# VIVA_PIC16_V5.net
KiCad netlist of a schematic drawn in EAGLE
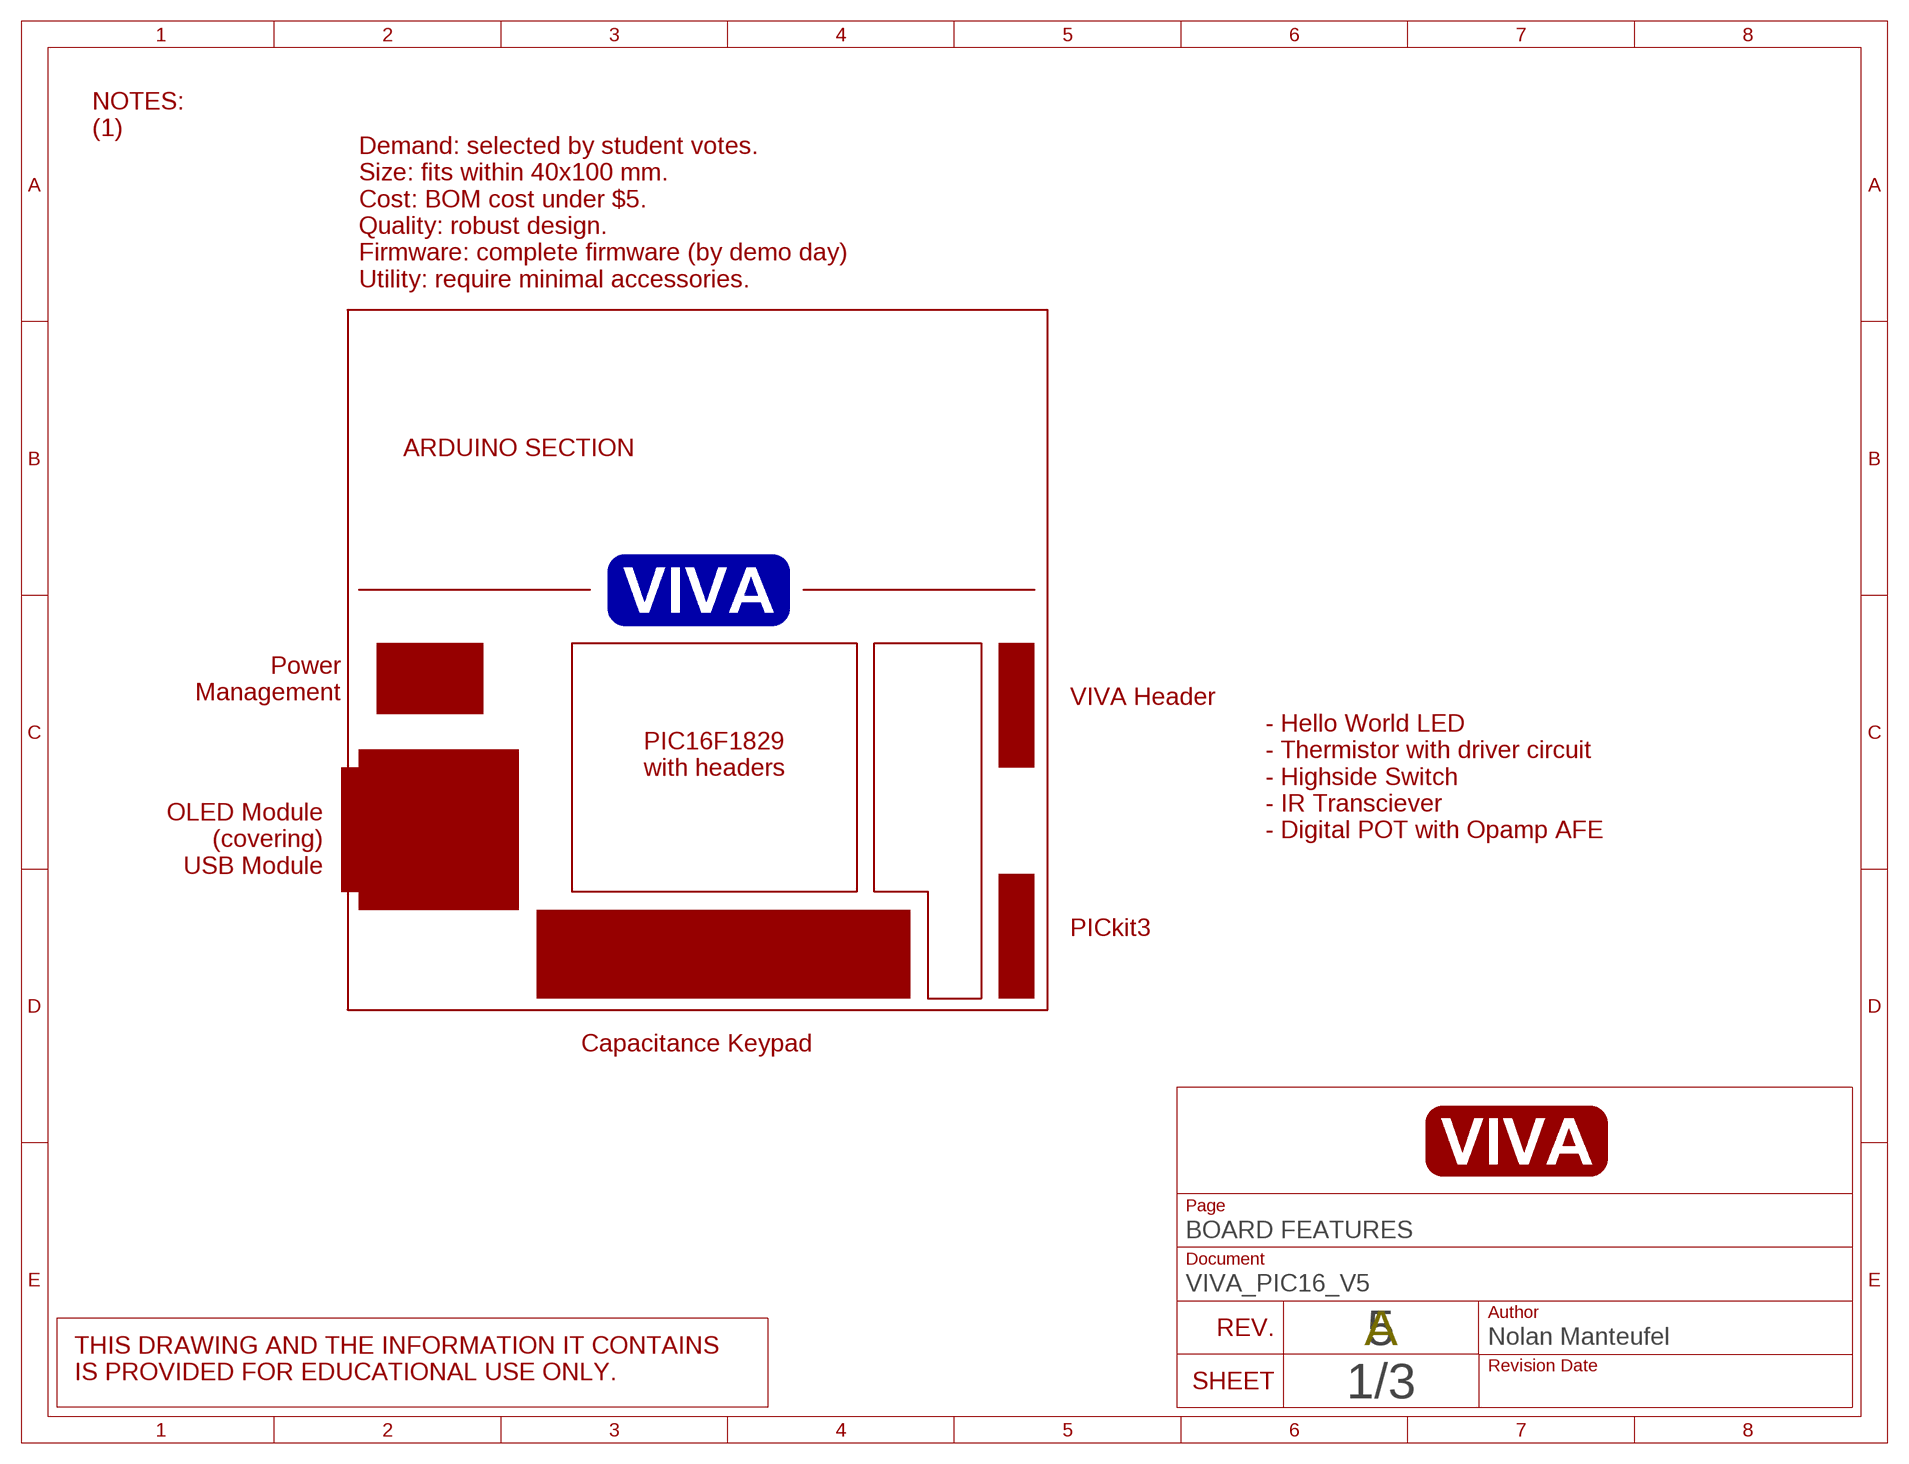
[diagram p0: schematic, sheet 1]
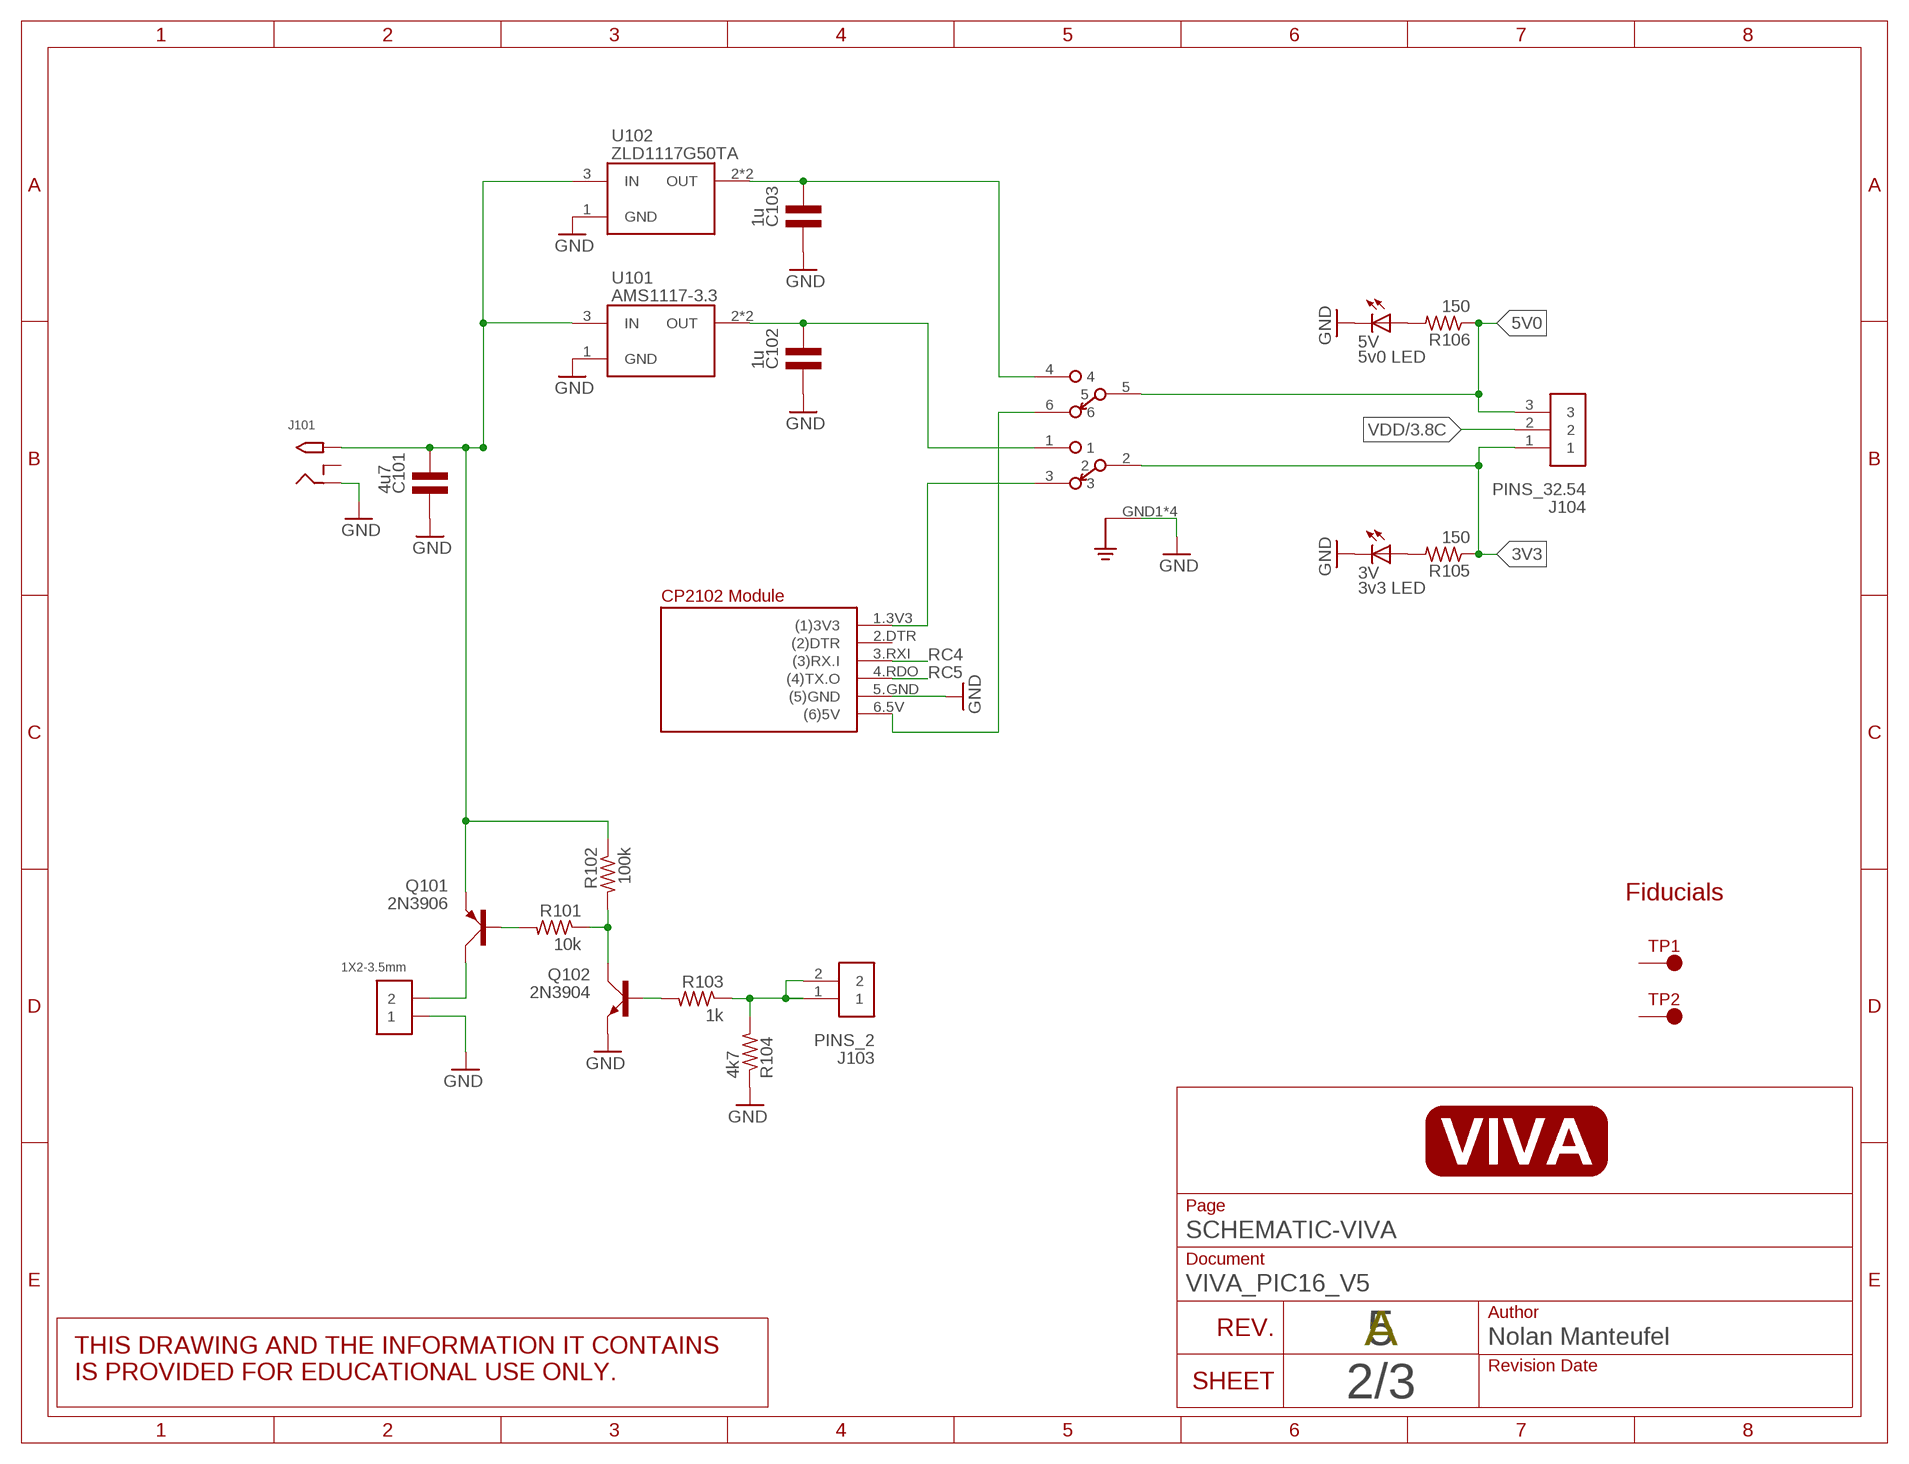
[diagram p1: schematic, sheet 2]
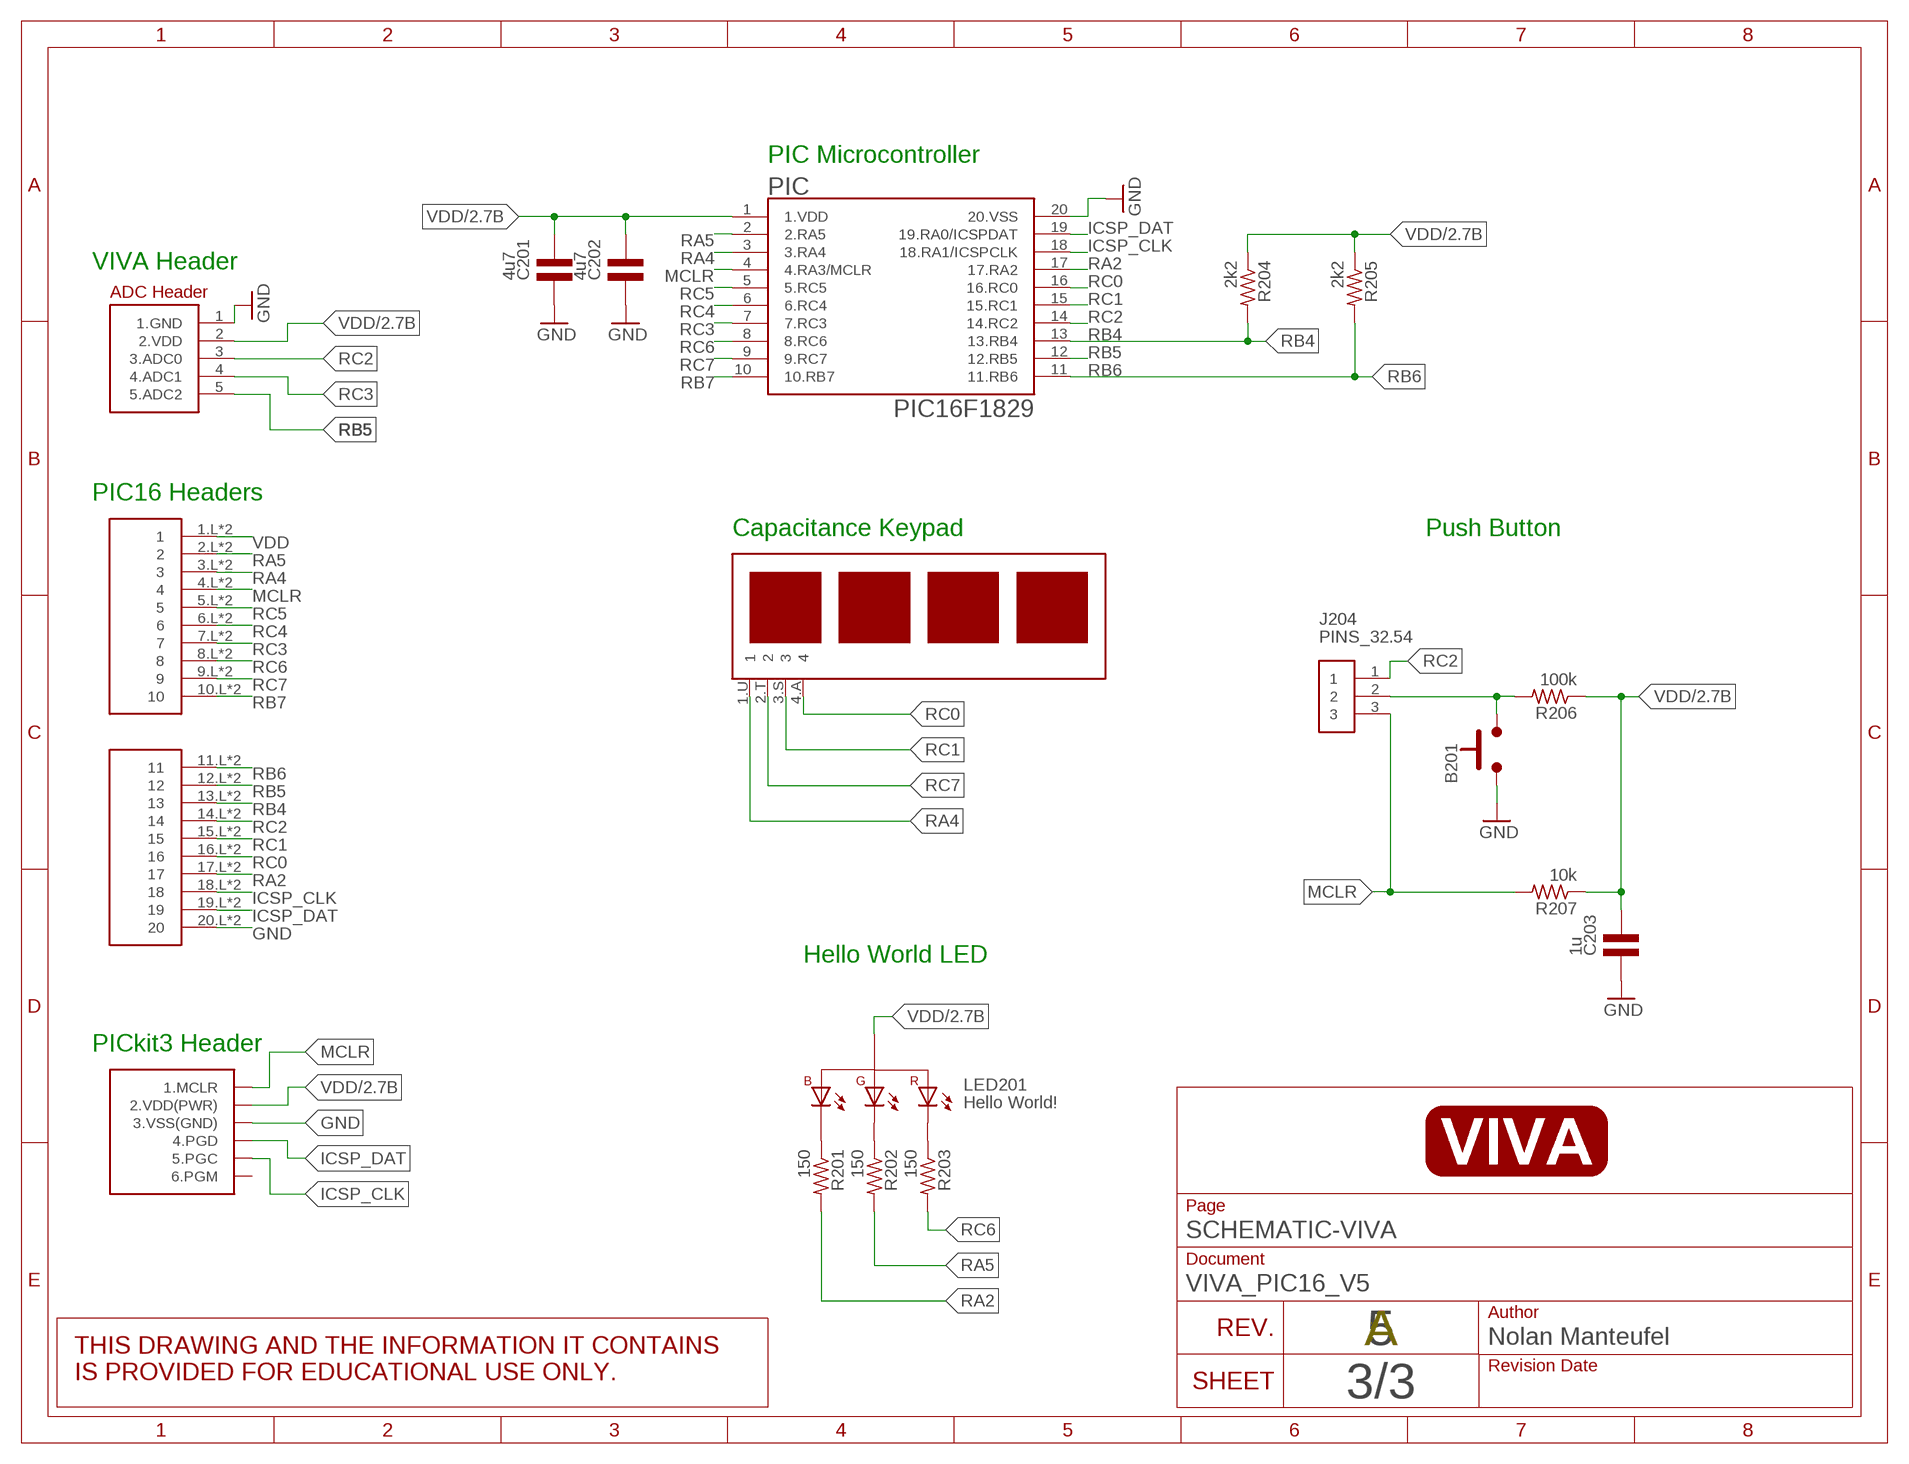
[diagram p2: schematic, sheet 3]

(export (version "E")
  (design (tool "Eeschema 10.0.6"))
  (components
    (comp (ref "U$1")
      (value "VIVA_LOGO")
      (footprint "eagle-import:VIVA_LOGO")
      (libsource (lib "eagle-import") (part "VIVA_LOGO"))
    )
    (comp (ref "B201")
      (value "PUSHBUTTON6X6MM")
      (footprint "eagle-import:6X6MM")
      (libsource (lib "eagle-import") (part "PUSHBUTTON6X6MM"))
    )
    (comp (ref "C201")
      (value "4u7")
      (footprint "eagle-import:C0805")
      (libsource (lib "eagle-import") (part "C0805"))
    )
    (comp (ref "C202")
      (value "4u7")
      (footprint "eagle-import:C0805")
      (libsource (lib "eagle-import") (part "C0805"))
    )
    (comp (ref "C203")
      (value "1u")
      (footprint "eagle-import:C0805")
      (libsource (lib "eagle-import") (part "C0805"))
    )
    (comp (ref "J201")
      (value "VIVA_PIC16")
      (footprint "eagle-import:VIVA_PIC16")
      (libsource (lib "eagle-import") (part "VIVA_PIC16"))
    )
    (comp (ref "J202")
      (value "VIVA-HEADER-ADCNONAME")
      (footprint "eagle-import:VIVA-HEADER-ADC-NONAME")
      (libsource (lib "eagle-import") (part "VIVA-HEADER-ADCNONAME"))
    )
    (comp (ref "J203")
      (value "PICKIT3")
      (footprint "eagle-import:PICKIT3")
      (libsource (lib "eagle-import") (part "PICKIT3"))
    )
    (comp (ref "J204")
      (value "PINS_32.54")
      (footprint "eagle-import:PINS_3")
      (libsource (lib "eagle-import") (part "PINS_32.54"))
    )
    (comp (ref "LED201")
      (value "Hello World!")
      (footprint "eagle-import:LED_RGB-5050")
      (libsource (lib "eagle-import") (part "RGB_LED"))
    )
    (comp (ref "PIC")
      (value "PIC16F1829")
      (footprint "eagle-import:SOP20-NEW")
      (libsource (lib "eagle-import") (part "PIC16F1829"))
    )
    (comp (ref "R201")
      (value "150")
      (footprint "eagle-import:R0805")
      (libsource (lib "eagle-import") (part "R-US_R0805"))
    )
    (comp (ref "R202")
      (value "150")
      (footprint "eagle-import:R0805")
      (libsource (lib "eagle-import") (part "R-US_R0805"))
    )
    (comp (ref "R203")
      (value "150")
      (footprint "eagle-import:R0805")
      (libsource (lib "eagle-import") (part "R-US_R0805"))
    )
    (comp (ref "R204")
      (value "2k2")
      (footprint "eagle-import:R0805")
      (libsource (lib "eagle-import") (part "R-US_R0805"))
    )
    (comp (ref "R205")
      (value "2k2")
      (footprint "eagle-import:R0805")
      (libsource (lib "eagle-import") (part "R-US_R0805"))
    )
    (comp (ref "R206")
      (value "100k")
      (footprint "eagle-import:R0805")
      (libsource (lib "eagle-import") (part "R-US_R0805"))
    )
    (comp (ref "R207")
      (value "10k")
      (footprint "eagle-import:R0805")
      (libsource (lib "eagle-import") (part "R-US_R0805"))
    )
    (comp (ref "U$201")
      (value "VIVA_UTSA-KEYPAD")
      (footprint "eagle-import:VIVA_UTSA-KEYPAD")
      (libsource (lib "eagle-import") (part "VIVA_UTSA-KEYPAD"))
    )
    (comp (ref "3V")
      (value "3v3 LED")
      (footprint "eagle-import:CHIPLED_0805")
      (libsource (lib "eagle-import") (part "LEDCHIPLED_0805"))
    )
    (comp (ref "5V")
      (value "5v0 LED")
      (footprint "eagle-import:CHIPLED_0805")
      (libsource (lib "eagle-import") (part "LEDCHIPLED_0805"))
    )
    (comp (ref "C101")
      (value "4u7")
      (footprint "eagle-import:C0805")
      (libsource (lib "eagle-import") (part "C0805"))
    )
    (comp (ref "C102")
      (value "1u")
      (footprint "eagle-import:C0805")
      (libsource (lib "eagle-import") (part "C0805"))
    )
    (comp (ref "C103")
      (value "1u")
      (footprint "eagle-import:C0805")
      (libsource (lib "eagle-import") (part "C0805"))
    )
    (comp (ref "J101")
      (value "2.1MMJACKTHM")
      (footprint "eagle-import:PJ-102A")
      (libsource (lib "eagle-import") (part "2.1MMJACKTHM"))
    )
    (comp (ref "J102")
      (value "1X2-3.5MM-3.5MM")
      (footprint "eagle-import:1X2-3.5MM")
      (libsource (lib "eagle-import") (part "1X2-3.5MM-3.5MM"))
    )
    (comp (ref "J103")
      (value "PINS_2")
      (footprint "eagle-import:PINS_2")
      (libsource (lib "eagle-import") (part "PINS_2"))
    )
    (comp (ref "J104")
      (value "PINS_32.54")
      (footprint "eagle-import:PINS_3")
      (libsource (lib "eagle-import") (part "PINS_32.54"))
    )
    (comp (ref "M101")
      (value "VIVA_USB-TTL")
      (footprint "eagle-import:VIVA_USB_TTL_SUBTEXT")
      (libsource (lib "eagle-import") (part "VIVA_USB-TTL"))
    )
    (comp (ref "Q101")
      (value "2N3906")
      (footprint "eagle-import:SOT23")
      (libsource (lib "eagle-import") (part "2N3906SOT23"))
    )
    (comp (ref "Q102")
      (value "2N3904")
      (footprint "eagle-import:SOT23")
      (libsource (lib "eagle-import") (part "2N3904SOT23"))
    )
    (comp (ref "R101")
      (value "10k")
      (footprint "eagle-import:R0805")
      (libsource (lib "eagle-import") (part "R-US_R0805"))
    )
    (comp (ref "R102")
      (value "100k")
      (footprint "eagle-import:R0805")
      (libsource (lib "eagle-import") (part "R-US_R0805"))
    )
    (comp (ref "R103")
      (value "1k")
      (footprint "eagle-import:R0805")
      (libsource (lib "eagle-import") (part "R-US_R0805"))
    )
    (comp (ref "R104")
      (value "4k7")
      (footprint "eagle-import:R0805")
      (libsource (lib "eagle-import") (part "R-US_R0805"))
    )
    (comp (ref "R105")
      (value "150")
      (footprint "eagle-import:R0805")
      (libsource (lib "eagle-import") (part "R-US_R0805"))
    )
    (comp (ref "R106")
      (value "150")
      (footprint "eagle-import:R0805")
      (libsource (lib "eagle-import") (part "R-US_R0805"))
    )
    (comp (ref "S101")
      (value "SWITCH_OS202013")
      (footprint "eagle-import:OS202013MT5QN1")
      (libsource (lib "eagle-import") (part "SWITCH_OS202013"))
    )
    (comp (ref "TP1")
      (value "TESTPOINTFIDUCIAL")
      (footprint "eagle-import:FIDUCIAL")
      (libsource (lib "eagle-import") (part "TESTPOINTFIDUCIAL"))
    )
    (comp (ref "TP2")
      (value "TESTPOINTFIDUCIAL")
      (footprint "eagle-import:FIDUCIAL")
      (libsource (lib "eagle-import") (part "TESTPOINTFIDUCIAL"))
    )
    (comp (ref "U101")
      (value "AMS1117-3.3")
      (footprint "eagle-import:SOT223")
      (libsource (lib "eagle-import") (part "REGULATOR_SCHLM1117"))
    )
    (comp (ref "U102")
      (value "ZLD1117G50TA")
      (footprint "eagle-import:SOT223")
      (libsource (lib "eagle-import") (part "REGULATOR_SCHLM1117"))
    )
  )
  (nets
    (net (code "1") (name "3V3") (class "Default")
      (node (ref "J104") (pin "1") (pinfunction "1_1") (pintype "bidirectional"))
      (node (ref "R105") (pin "1") (pinfunction "1_1") (pintype "passive"))
      (node (ref "S101") (pin "2") (pinfunction "2_2") (pintype "bidirectional"))
    )
    (net (code "2") (name "5V0") (class "Default")
      (node (ref "J104") (pin "3") (pinfunction "3_3") (pintype "bidirectional"))
      (node (ref "R106") (pin "1") (pinfunction "1_1") (pintype "passive"))
      (node (ref "S101") (pin "5") (pinfunction "5_5") (pintype "bidirectional"))
    )
    (net (code "3") (name "GND") (class "Default")
      (node (ref "3V") (pin "C") (pinfunction "C_C") (pintype "passive"))
      (node (ref "5V") (pin "C") (pinfunction "C_C") (pintype "passive"))
      (node (ref "B201") (pin "1.A") (pinfunction "1_1.A") (pintype "bidirectional"))
      (node (ref "B201") (pin "2.A") (pinfunction "1_2.A") (pintype "bidirectional"))
      (node (ref "C101") (pin "1") (pinfunction "P$1_1") (pintype "passive"))
      (node (ref "C102") (pin "1") (pinfunction "P$1_1") (pintype "passive"))
      (node (ref "C103") (pin "1") (pinfunction "P$1_1") (pintype "passive"))
      (node (ref "C201") (pin "1") (pinfunction "P$1_1") (pintype "passive"))
      (node (ref "C202") (pin "1") (pinfunction "P$1_1") (pintype "passive"))
      (node (ref "C203") (pin "1") (pinfunction "P$1_1") (pintype "passive"))
      (node (ref "J101") (pin "RING") (pinfunction "RING_RING") (pintype "bidirectional"))
      (node (ref "J102") (pin "1") (pinfunction "1_1") (pintype "passive"))
      (node (ref "J201") (pin "20.L") (pinfunction "20_20.L") (pintype "bidirectional"))
      (node (ref "J201") (pin "20.R") (pinfunction "20_20.R") (pintype "bidirectional"))
      (node (ref "J202") (pin "1") (pinfunction "1.GND_1") (pintype "bidirectional"))
      (node (ref "J203") (pin "3") (pinfunction "3.VSS(GND)_3") (pintype "bidirectional"))
      (node (ref "M101") (pin "5.GND") (pinfunction "(5)GND_5.GND") (pintype "bidirectional"))
      (node (ref "PIC") (pin "20") (pinfunction "20.VSS_20") (pintype "bidirectional"))
      (node (ref "Q102") (pin "2") (pinfunction "E_2") (pintype "passive"))
      (node (ref "R104") (pin "1") (pinfunction "1_1") (pintype "passive"))
      (node (ref "S101") (pin "GND1") (pinfunction "GND_GND1") (pintype "bidirectional"))
      (node (ref "S101") (pin "GND2") (pinfunction "GND_GND2") (pintype "bidirectional"))
      (node (ref "S101") (pin "GND3") (pinfunction "GND_GND3") (pintype "bidirectional"))
      (node (ref "S101") (pin "GND4") (pinfunction "GND_GND4") (pintype "bidirectional"))
      (node (ref "U101") (pin "1") (pinfunction "GND_1") (pintype "bidirectional"))
      (node (ref "U102") (pin "1") (pinfunction "GND_1") (pintype "bidirectional"))
    )
    (net (code "4") (name "ICSP_CLK") (class "Default")
      (node (ref "J201") (pin "18.L") (pinfunction "18_18.L") (pintype "bidirectional"))
      (node (ref "J201") (pin "18.R") (pinfunction "18_18.R") (pintype "bidirectional"))
      (node (ref "J203") (pin "5") (pinfunction "5.PGC_5") (pintype "bidirectional"))
      (node (ref "PIC") (pin "18") (pinfunction "18.RA1/ICSPCLK_18") (pintype "bidirectional"))
    )
    (net (code "5") (name "ICSP_DAT") (class "Default")
      (node (ref "J201") (pin "19.L") (pinfunction "19_19.L") (pintype "bidirectional"))
      (node (ref "J201") (pin "19.R") (pinfunction "19_19.R") (pintype "bidirectional"))
      (node (ref "J203") (pin "4") (pinfunction "4.PGD_4") (pintype "bidirectional"))
      (node (ref "PIC") (pin "19") (pinfunction "19.RA0/ICSPDAT_19") (pintype "bidirectional"))
    )
    (net (code "6") (name "MCLR") (class "Default")
      (node (ref "J201") (pin "4.L") (pinfunction "4_4.L") (pintype "bidirectional"))
      (node (ref "J201") (pin "4.R") (pinfunction "4_4.R") (pintype "bidirectional"))
      (node (ref "J203") (pin "1") (pinfunction "1.MCLR_1") (pintype "bidirectional"))
      (node (ref "J204") (pin "3") (pinfunction "3_3") (pintype "bidirectional"))
      (node (ref "PIC") (pin "4") (pinfunction "4.RA3/MCLR_4") (pintype "bidirectional"))
      (node (ref "R207") (pin "2") (pinfunction "2_2") (pintype "passive"))
    )
    (net (code "7") (name "Net-(3V-PadA)") (class "Default")
      (node (ref "3V") (pin "A") (pinfunction "A_A") (pintype "passive"))
      (node (ref "R105") (pin "2") (pinfunction "2_2") (pintype "passive"))
    )
    (net (code "8") (name "Net-(5V-PadA)") (class "Default")
      (node (ref "5V") (pin "A") (pinfunction "A_A") (pintype "passive"))
      (node (ref "R106") (pin "2") (pinfunction "2_2") (pintype "passive"))
    )
    (net (code "9") (name "Net-(B201-2-Pad3.B)") (class "Default")
      (node (ref "B201") (pin "3.B") (pinfunction "2_3.B") (pintype "bidirectional"))
      (node (ref "B201") (pin "4.B") (pinfunction "2_4.B") (pintype "bidirectional"))
      (node (ref "J204") (pin "2") (pinfunction "2_2") (pintype "bidirectional"))
      (node (ref "R206") (pin "2") (pinfunction "2_2") (pintype "passive"))
    )
    (net (code "10") (name "Net-(C101-P$2)") (class "Default")
      (node (ref "C101") (pin "2") (pinfunction "P$2_2") (pintype "passive"))
      (node (ref "J101") (pin "TIP") (pinfunction "TIP_TIP") (pintype "bidirectional"))
      (node (ref "Q101") (pin "2") (pinfunction "E_2") (pintype "passive"))
      (node (ref "R102") (pin "1") (pinfunction "1_1") (pintype "passive"))
      (node (ref "U101") (pin "3") (pinfunction "IN_3") (pintype "bidirectional"))
      (node (ref "U102") (pin "3") (pinfunction "IN_3") (pintype "bidirectional"))
    )
    (net (code "11") (name "Net-(C102-P$2)") (class "Default")
      (node (ref "C102") (pin "2") (pinfunction "P$2_2") (pintype "passive"))
      (node (ref "S101") (pin "1") (pinfunction "1_1") (pintype "bidirectional"))
      (node (ref "U101") (pin "2") (pinfunction "OUT_2") (pintype "bidirectional"))
      (node (ref "U101") (pin "4.TAB") (pinfunction "OUT_4.TAB") (pintype "bidirectional"))
    )
    (net (code "12") (name "Net-(C103-P$2)") (class "Default")
      (node (ref "C103") (pin "2") (pinfunction "P$2_2") (pintype "passive"))
      (node (ref "S101") (pin "4") (pinfunction "4_4") (pintype "bidirectional"))
      (node (ref "U102") (pin "2") (pinfunction "OUT_2") (pintype "bidirectional"))
      (node (ref "U102") (pin "4.TAB") (pinfunction "OUT_4.TAB") (pintype "bidirectional"))
    )
    (net (code "13") (name "Net-(J103-Pad1)") (class "Default")
      (node (ref "J103") (pin "1") (pinfunction "1_1") (pintype "bidirectional"))
      (node (ref "J103") (pin "2") (pinfunction "2_2") (pintype "bidirectional"))
      (node (ref "R103") (pin "1") (pinfunction "1_1") (pintype "passive"))
      (node (ref "R104") (pin "2") (pinfunction "2_2") (pintype "passive"))
    )
    (net (code "14") (name "Net-(LED201-Pad1.R-)") (class "Default")
      (node (ref "LED201") (pin "1.R-") (pinfunction "1.R-_1.R-") (pintype "passive"))
      (node (ref "R203") (pin "1") (pinfunction "1_1") (pintype "passive"))
    )
    (net (code "15") (name "Net-(LED201-Pad2.G-)") (class "Default")
      (node (ref "LED201") (pin "2.G-") (pinfunction "2.G-_2.G-") (pintype "passive"))
      (node (ref "R202") (pin "1") (pinfunction "1_1") (pintype "passive"))
    )
    (net (code "16") (name "Net-(LED201-Pad4.B-)") (class "Default")
      (node (ref "LED201") (pin "4.B-") (pinfunction "4.B-_4.B-") (pintype "passive"))
      (node (ref "R201") (pin "1") (pinfunction "1_1") (pintype "passive"))
    )
    (net (code "17") (name "Net-(M101-(1)3V3)") (class "Default")
      (node (ref "M101") (pin "1.3V3") (pinfunction "(1)3V3_1.3V3") (pintype "bidirectional"))
      (node (ref "S101") (pin "3") (pinfunction "3_3") (pintype "bidirectional"))
    )
    (net (code "18") (name "Net-(M101-(6)5V)") (class "Default")
      (node (ref "M101") (pin "6.5V") (pinfunction "(6)5V_6.5V") (pintype "bidirectional"))
      (node (ref "S101") (pin "6") (pinfunction "6_6") (pintype "bidirectional"))
    )
    (net (code "19") (name "Net-(Q101-B)") (class "Default")
      (node (ref "Q101") (pin "1") (pinfunction "B_1") (pintype "passive"))
      (node (ref "R101") (pin "2") (pinfunction "2_2") (pintype "passive"))
    )
    (net (code "20") (name "Net-(Q101-C)") (class "Default")
      (node (ref "J102") (pin "2") (pinfunction "2_2") (pintype "passive"))
      (node (ref "Q101") (pin "3") (pinfunction "C_3") (pintype "passive"))
    )
    (net (code "21") (name "Net-(Q102-B)") (class "Default")
      (node (ref "Q102") (pin "1") (pinfunction "B_1") (pintype "passive"))
      (node (ref "R103") (pin "2") (pinfunction "2_2") (pintype "passive"))
    )
    (net (code "22") (name "Net-(Q102-C)") (class "Default")
      (node (ref "Q102") (pin "3") (pinfunction "C_3") (pintype "passive"))
      (node (ref "R101") (pin "1") (pinfunction "1_1") (pintype "passive"))
      (node (ref "R102") (pin "2") (pinfunction "2_2") (pintype "passive"))
    )
    (net (code "23") (name "RA2") (class "Default")
      (node (ref "J201") (pin "17.L") (pinfunction "17_17.L") (pintype "bidirectional"))
      (node (ref "J201") (pin "17.R") (pinfunction "17_17.R") (pintype "bidirectional"))
      (node (ref "PIC") (pin "17") (pinfunction "17.RA2_17") (pintype "bidirectional"))
      (node (ref "R201") (pin "2") (pinfunction "2_2") (pintype "passive"))
    )
    (net (code "24") (name "RA4") (class "Default")
      (node (ref "J201") (pin "3.L") (pinfunction "3_3.L") (pintype "bidirectional"))
      (node (ref "J201") (pin "3.R") (pinfunction "3_3.R") (pintype "bidirectional"))
      (node (ref "PIC") (pin "3") (pinfunction "3.RA4_3") (pintype "bidirectional"))
      (node (ref "U$201") (pin "1.U") (pinfunction "1_1.U") (pintype "bidirectional"))
    )
    (net (code "25") (name "RA5") (class "Default")
      (node (ref "J201") (pin "2.L") (pinfunction "2_2.L") (pintype "bidirectional"))
      (node (ref "J201") (pin "2.R") (pinfunction "2_2.R") (pintype "bidirectional"))
      (node (ref "PIC") (pin "2") (pinfunction "2.RA5_2") (pintype "bidirectional"))
      (node (ref "R202") (pin "2") (pinfunction "2_2") (pintype "passive"))
    )
    (net (code "26") (name "RB4") (class "Default")
      (node (ref "J201") (pin "13.L") (pinfunction "13_13.L") (pintype "bidirectional"))
      (node (ref "J201") (pin "13.R") (pinfunction "13_13.R") (pintype "bidirectional"))
      (node (ref "PIC") (pin "13") (pinfunction "13.RB4_13") (pintype "bidirectional"))
      (node (ref "R204") (pin "2") (pinfunction "2_2") (pintype "passive"))
    )
    (net (code "27") (name "RB5") (class "Default")
      (node (ref "J201") (pin "12.L") (pinfunction "12_12.L") (pintype "bidirectional"))
      (node (ref "J201") (pin "12.R") (pinfunction "12_12.R") (pintype "bidirectional"))
      (node (ref "J202") (pin "5") (pinfunction "5.ADC2_5") (pintype "bidirectional"))
      (node (ref "PIC") (pin "12") (pinfunction "12.RB5_12") (pintype "bidirectional"))
    )
    (net (code "28") (name "RB6") (class "Default")
      (node (ref "J201") (pin "11.L") (pinfunction "11_11.L") (pintype "bidirectional"))
      (node (ref "J201") (pin "11.R") (pinfunction "11_11.R") (pintype "bidirectional"))
      (node (ref "PIC") (pin "11") (pinfunction "11.RB6_11") (pintype "bidirectional"))
      (node (ref "R205") (pin "2") (pinfunction "2_2") (pintype "passive"))
    )
    (net (code "29") (name "RB7") (class "Default")
      (node (ref "J201") (pin "10.L") (pinfunction "10_10.L") (pintype "bidirectional"))
      (node (ref "J201") (pin "10.R") (pinfunction "10_10.R") (pintype "bidirectional"))
      (node (ref "PIC") (pin "10") (pinfunction "10.RB7_10") (pintype "bidirectional"))
    )
    (net (code "30") (name "RC0") (class "Default")
      (node (ref "J201") (pin "16.L") (pinfunction "16_16.L") (pintype "bidirectional"))
      (node (ref "J201") (pin "16.R") (pinfunction "16_16.R") (pintype "bidirectional"))
      (node (ref "PIC") (pin "16") (pinfunction "16.RC0_16") (pintype "bidirectional"))
      (node (ref "U$201") (pin "4.A") (pinfunction "4_4.A") (pintype "bidirectional"))
    )
    (net (code "31") (name "RC1") (class "Default")
      (node (ref "J201") (pin "15.L") (pinfunction "15_15.L") (pintype "bidirectional"))
      (node (ref "J201") (pin "15.R") (pinfunction "15_15.R") (pintype "bidirectional"))
      (node (ref "PIC") (pin "15") (pinfunction "15.RC1_15") (pintype "bidirectional"))
      (node (ref "U$201") (pin "3.S") (pinfunction "3_3.S") (pintype "bidirectional"))
    )
    (net (code "32") (name "RC2") (class "Default")
      (node (ref "J201") (pin "14.L") (pinfunction "14_14.L") (pintype "bidirectional"))
      (node (ref "J201") (pin "14.R") (pinfunction "14_14.R") (pintype "bidirectional"))
      (node (ref "J202") (pin "3") (pinfunction "3.ADC0_3") (pintype "bidirectional"))
      (node (ref "J204") (pin "1") (pinfunction "1_1") (pintype "bidirectional"))
      (node (ref "PIC") (pin "14") (pinfunction "14.RC2_14") (pintype "bidirectional"))
    )
    (net (code "33") (name "RC3") (class "Default")
      (node (ref "J201") (pin "7.L") (pinfunction "7_7.L") (pintype "bidirectional"))
      (node (ref "J201") (pin "7.R") (pinfunction "7_7.R") (pintype "bidirectional"))
      (node (ref "J202") (pin "4") (pinfunction "4.ADC1_4") (pintype "bidirectional"))
      (node (ref "PIC") (pin "7") (pinfunction "7.RC3_7") (pintype "bidirectional"))
    )
    (net (code "34") (name "RC4") (class "Default")
      (node (ref "J201") (pin "6.L") (pinfunction "6_6.L") (pintype "bidirectional"))
      (node (ref "J201") (pin "6.R") (pinfunction "6_6.R") (pintype "bidirectional"))
      (node (ref "M101") (pin "3.RXI") (pinfunction "(3)RX.I_3.RXI") (pintype "bidirectional"))
      (node (ref "PIC") (pin "6") (pinfunction "6.RC4_6") (pintype "bidirectional"))
    )
    (net (code "35") (name "RC5") (class "Default")
      (node (ref "J201") (pin "5.L") (pinfunction "5_5.L") (pintype "bidirectional"))
      (node (ref "J201") (pin "5.R") (pinfunction "5_5.R") (pintype "bidirectional"))
      (node (ref "M101") (pin "4.RDO") (pinfunction "(4)TX.O_4.RDO") (pintype "bidirectional"))
      (node (ref "PIC") (pin "5") (pinfunction "5.RC5_5") (pintype "bidirectional"))
    )
    (net (code "36") (name "RC6") (class "Default")
      (node (ref "J201") (pin "8.L") (pinfunction "8_8.L") (pintype "bidirectional"))
      (node (ref "J201") (pin "8.R") (pinfunction "8_8.R") (pintype "bidirectional"))
      (node (ref "PIC") (pin "8") (pinfunction "8.RC6_8") (pintype "bidirectional"))
      (node (ref "R203") (pin "2") (pinfunction "2_2") (pintype "passive"))
    )
    (net (code "37") (name "RC7") (class "Default")
      (node (ref "J201") (pin "9.L") (pinfunction "9_9.L") (pintype "bidirectional"))
      (node (ref "J201") (pin "9.R") (pinfunction "9_9.R") (pintype "bidirectional"))
      (node (ref "PIC") (pin "9") (pinfunction "9.RC7_9") (pintype "bidirectional"))
      (node (ref "U$201") (pin "2.T") (pinfunction "2_2.T") (pintype "bidirectional"))
    )
    (net (code "38") (name "VDD") (class "Default")
      (node (ref "C201") (pin "2") (pinfunction "P$2_2") (pintype "passive"))
      (node (ref "C202") (pin "2") (pinfunction "P$2_2") (pintype "passive"))
      (node (ref "C203") (pin "2") (pinfunction "P$2_2") (pintype "passive"))
      (node (ref "J104") (pin "2") (pinfunction "2_2") (pintype "bidirectional"))
      (node (ref "J201") (pin "1.L") (pinfunction "1_1.L") (pintype "bidirectional"))
      (node (ref "J201") (pin "1.R") (pinfunction "1_1.R") (pintype "bidirectional"))
      (node (ref "J202") (pin "2") (pinfunction "2.VDD_2") (pintype "bidirectional"))
      (node (ref "J203") (pin "2") (pinfunction "2.VDD(PWR)_2") (pintype "bidirectional"))
      (node (ref "LED201") (pin "3.+") (pinfunction "3.+_3.+") (pintype "passive"))
      (node (ref "PIC") (pin "1") (pinfunction "1.VDD_1") (pintype "bidirectional"))
      (node (ref "R204") (pin "1") (pinfunction "1_1") (pintype "passive"))
      (node (ref "R205") (pin "1") (pinfunction "1_1") (pintype "passive"))
      (node (ref "R206") (pin "1") (pinfunction "1_1") (pintype "passive"))
      (node (ref "R207") (pin "1") (pinfunction "1_1") (pintype "passive"))
    )
    (net (code "39") (name "unconnected-(J101-PadRING_SW)") (class "Default")
      (node (ref "J101") (pin "RING_SW") (pinfunction "RING_SW_RING_SW") (pintype "bidirectional"))
    )
    (net (code "40") (name "unconnected-(J203-6.PGM-Pad6)") (class "Default")
      (node (ref "J203") (pin "6") (pinfunction "6.PGM_6") (pintype "bidirectional"))
    )
    (net (code "41") (name "unconnected-(M101-(2)DTR-Pad2.DTR)") (class "Default")
      (node (ref "M101") (pin "2.DTR") (pinfunction "(2)DTR_2.DTR") (pintype "bidirectional"))
    )
    (net (code "42") (name "unconnected-(TP1-P$1-PadFIDUCIAL)") (class "Default")
      (node (ref "TP1") (pin "FIDUCIAL") (pinfunction "P$1_FIDUCIAL") (pintype "bidirectional"))
    )
    (net (code "43") (name "unconnected-(TP2-P$1-PadFIDUCIAL)") (class "Default")
      (node (ref "TP2") (pin "FIDUCIAL") (pinfunction "P$1_FIDUCIAL") (pintype "bidirectional"))
    )
  )
)
